# Sheet2.net
KiCad netlist of a schematic drawn in Altium Designer
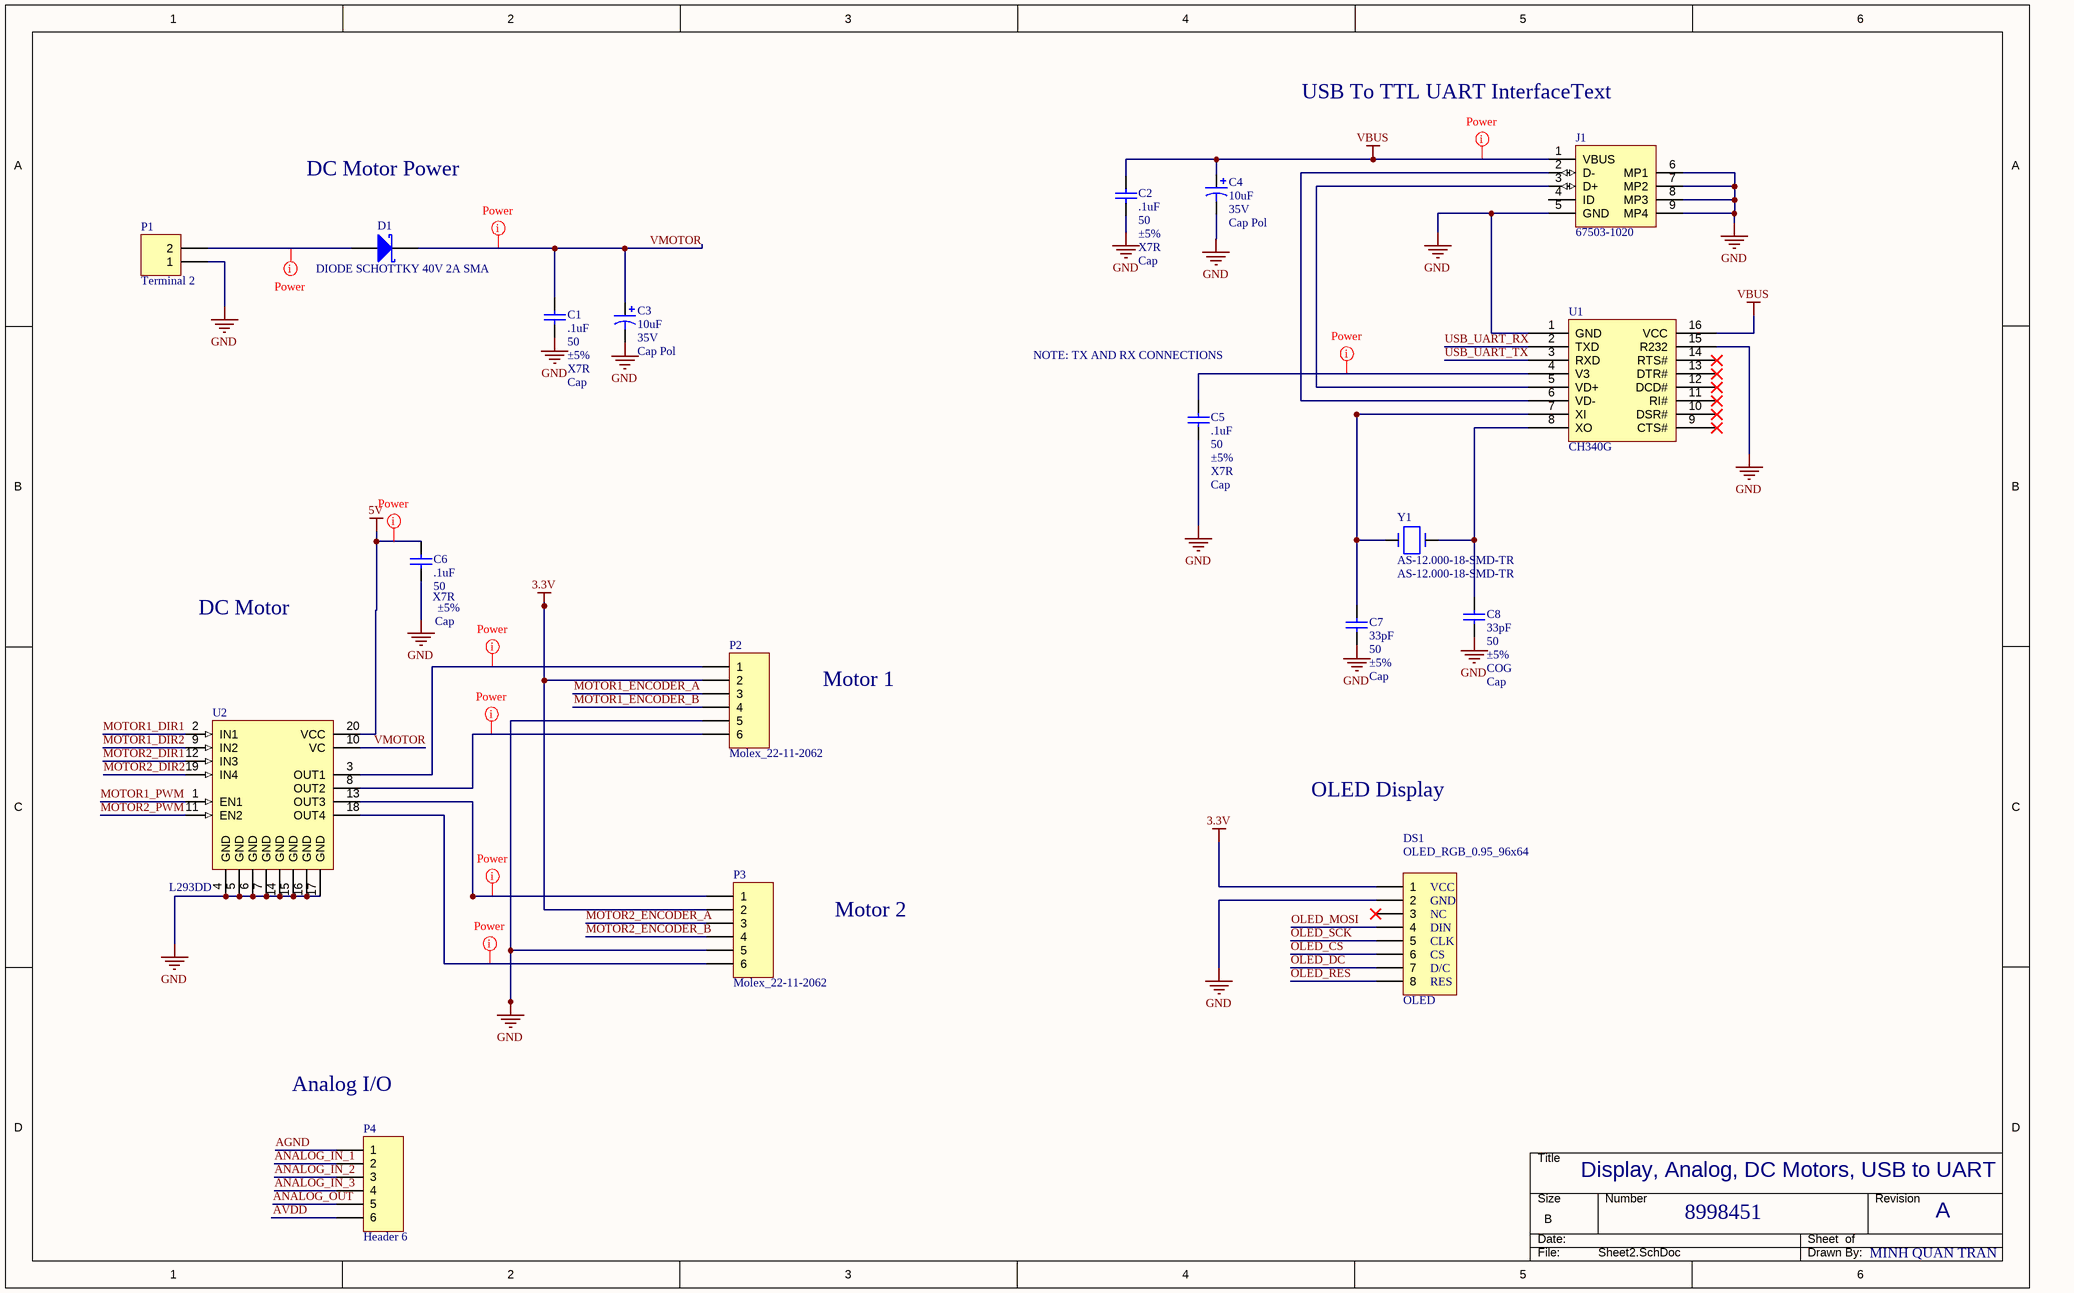
[diagram p0: Sheet2.SchDoc]

(export (version "E")
  (design (tool "Eeschema 10.0.6"))
  (components
    (comp (ref "C1")
      (value "Cap")
      (footprint "CAPC2012X09M")
      (description "CAP CER .1uF 50v X7R 0805")
      (fields
        (field (name "ALTIUM_VALUE") ".1uF")
        (field (name "WV") "50")
        (field (name "TOLERANCE") "±5%")
        (field (name "TYPE") "X7R")
        (field (name "MPN") "C0805C104J5RACTU")
      )
      (libsource (lib "esd_library") (part "CAP-X7R-.1uF-50V-±5%"))
    )
    (comp (ref "C2")
      (value "Cap")
      (footprint "CAPC2012X09M")
      (description "CAP CER .1uF 50v X7R 0805")
      (fields
        (field (name "ALTIUM_VALUE") ".1uF")
        (field (name "WV") "50")
        (field (name "TOLERANCE") "±5%")
        (field (name "TYPE") "X7R")
        (field (name "MPN") "C0805C104J5RACTU")
      )
      (libsource (lib "esd_library") (part "CAP-X7R-.1uF-50V-±5%"))
    )
    (comp (ref "C3")
      (value "Cap Pol")
      (footprint "CAPACITOR_5MM")
      (description "CAP 85C 10uF ±20% 35V WX Series Aluminum Electrolytic")
      (fields
        (field (name "ALTIUM_VALUE") "10uF")
        (field (name "VOLTAGE") "35V")
        (field (name "MPN") "UWX1V100MCL1GB")
      )
      (libsource (lib "esd_library") (part "Cap Polar-10uF-35V"))
    )
    (comp (ref "C4")
      (value "Cap Pol")
      (footprint "CAPACITOR_5MM")
      (description "CAP 85C 10uF ±20% 35V WX Series Aluminum Electrolytic")
      (fields
        (field (name "ALTIUM_VALUE") "10uF")
        (field (name "VOLTAGE") "35V")
        (field (name "MPN") "UWX1V100MCL1GB")
      )
      (libsource (lib "esd_library") (part "Cap Polar-10uF-35V"))
    )
    (comp (ref "C5")
      (value "Cap")
      (footprint "CAPC2012X09M")
      (description "CAP CER .1uF 50v X7R 0805")
      (fields
        (field (name "ALTIUM_VALUE") ".1uF")
        (field (name "WV") "50")
        (field (name "TOLERANCE") "±5%")
        (field (name "TYPE") "X7R")
        (field (name "MPN") "C0805C104J5RACTU")
      )
      (libsource (lib "esd_library") (part "CAP-X7R-.1uF-50V-±5%"))
    )
    (comp (ref "C6")
      (value "Cap")
      (footprint "CAPC2012X09M")
      (description "CAP CER .1uF 50v X7R 0805")
      (fields
        (field (name "ALTIUM_VALUE") ".1uF")
        (field (name "WV") "50")
        (field (name "TOLERANCE") "±5%")
        (field (name "TYPE") "X7R")
        (field (name "MPN") "C0805C104J5RACTU")
      )
      (libsource (lib "esd_library") (part "CAP-X7R-.1uF-50V-±5%"))
    )
    (comp (ref "C7")
      (value "Cap")
      (footprint "CAPC2012X09M")
      (description "CAP CER 33pF 50v COG 0805")
      (fields
        (field (name "ALTIUM_VALUE") "33pF")
        (field (name "WV") "50")
        (field (name "TOLERANCE") "±5%")
        (field (name "MPN") "C0805C330J5GACTU")
      )
      (libsource (lib "esd_library") (part "CAP-COG-33pF-50V-±5%"))
    )
    (comp (ref "C8")
      (value "Cap")
      (footprint "CAPC2012X09M")
      (description "CAP CER 33pF 50v COG 0805")
      (fields
        (field (name "ALTIUM_VALUE") "33pF")
        (field (name "WV") "50")
        (field (name "TOLERANCE") "±5%")
        (field (name "TYPE") "COG")
        (field (name "MPN") "C0805C330J5GACTU")
      )
      (libsource (lib "esd_library") (part "CAP-COG-33pF-50V-±5%"))
    )
    (comp (ref "D1")
      (value "DIODE SCHOTTKY 40V 2A SMA")
      (footprint "DIOM4326X23M")
      (description "Schottky Rectifier")
      (fields (field (name "MPN") "B240A-13-F"))
      (libsource (lib "esd_library") (part "DIODE SCHOTTKY 40V 2A SMA"))
    )
    (comp (ref "DS1")
      (value "OLED")
      (footprint "OLED_RGB_0.95_96x64_Waveshare")
      (description "Waveshare 0.95 inch OLED Module")
      (fields (field (name "MPN") "PPPC081LFBN-RC"))
      (libsource (lib "esd_library") (part "OLED_RGB_0.95_96x64_Waveshare"))
    )
    (comp (ref "J1")
      (value "67503-1020")
      (footprint "MOLX-67503-1020_V")
      (description "USB, MINI, SMD, RA KME04-USBMU03A01")
      (fields (field (name "MANUFACTURER") "Molex"))
      (libsource (lib "esd_library") (part "MOLX-67503-1020"))
    )
    (comp (ref "P1")
      (value "Terminal 2")
      (footprint "TYCO_282841_2")
      (description "Terminal, 2-Pin")
      (fields (field (name "MPN") "282841-2") (field (name "PUBLISHER") "Altium Limited"))
      (libsource (lib "esd_library") (part "Terminal 2"))
    )
    (comp (ref "P2")
      (value "Molex_22-11-2062")
      (footprint "MOLEX_22-11-2062")
      (description "CONN HEADER 6POS .100 VERT GOLD")
      (fields (field (name "MPN") "0022112062"))
      (libsource (lib "esd_library") (part "Molex_22-11-2062"))
    )
    (comp (ref "P3")
      (value "Molex_22-11-2062")
      (footprint "MOLEX_22-11-2062")
      (description "CONN HEADER 6POS .100 VERT GOLD")
      (fields (field (name "MPN") "0022112062"))
      (libsource (lib "esd_library") (part "Molex_22-11-2062"))
    )
    (comp (ref "P4")
      (value "Header 6")
      (footprint "HDR1X6")
      (description "Header, 6-Pin Male")
      (fields (field (name "MPN") "PEC06SFAN"))
      (libsource (lib "esd_library") (part "Header 6"))
    )
    (comp (ref "U1")
      (value "CH340G")
      (footprint "NSO16_L")
      (description "USB to serial chip")
      (libsource (lib "esd_library") (part "CH340G"))
    )
    (comp (ref "U2")
      (value "L293DD")
      (footprint "SO20_N")
      (description "IC MOTOR DRIVER PAR 20-SOIC")
      (fields (field (name "MPN") "L293DD013TR") (field (name "PUBLISHER") "Altium Limited"))
      (libsource (lib "esd_library") (part "L293DD"))
    )
    (comp (ref "Y1")
      (value "AS-12.000-18-SMD-TR")
      (footprint "HCS-49/U")
      (description "CRYSTAL 12.0000MHZ 18PF SMD")
      (fields (field (name "MPN") "AS-12.000-18-SMD-TR"))
      (libsource (lib "esd_library") (part "AS-12.000-18-SMD-TR"))
    )
  )
  (nets
    (net (code "1") (name "/AGND") (class "Default")
      (node (ref "P4") (pin "1") (pinfunction "1_1") (pintype "passive"))
    )
    (net (code "2") (name "/ANALOG_IN_1") (class "Default")
      (node (ref "P4") (pin "2") (pinfunction "2_2") (pintype "passive"))
    )
    (net (code "3") (name "/ANALOG_IN_2") (class "Default")
      (node (ref "P4") (pin "3") (pinfunction "3_3") (pintype "passive"))
    )
    (net (code "4") (name "/ANALOG_IN_3") (class "Default")
      (node (ref "P4") (pin "4") (pinfunction "4_4") (pintype "passive"))
    )
    (net (code "5") (name "/ANALOG_OUT") (class "Default")
      (node (ref "P4") (pin "5") (pinfunction "5_5") (pintype "passive"))
    )
    (net (code "6") (name "/AVDD") (class "Default")
      (node (ref "P4") (pin "6") (pinfunction "6_6") (pintype "passive"))
    )
    (net (code "7") (name "/MOTOR1_DIR1") (class "Default")
      (node (ref "U2") (pin "2") (pinfunction "IN1_2") (pintype "input"))
    )
    (net (code "8") (name "/MOTOR1_DIR2") (class "Default")
      (node (ref "U2") (pin "9") (pinfunction "IN2_9") (pintype "input"))
    )
    (net (code "9") (name "/MOTOR1_ENCODER_A") (class "Default")
      (node (ref "P2") (pin "3") (pinfunction "3_3") (pintype "passive"))
    )
    (net (code "10") (name "/MOTOR1_ENCODER_B") (class "Default")
      (node (ref "P2") (pin "4") (pinfunction "4_4") (pintype "passive"))
    )
    (net (code "11") (name "/MOTOR1_PWM") (class "Default")
      (node (ref "U2") (pin "1") (pinfunction "EN1_1") (pintype "input"))
    )
    (net (code "12") (name "/MOTOR2_DIR1") (class "Default")
      (node (ref "U2") (pin "12") (pinfunction "IN3_12") (pintype "input"))
    )
    (net (code "13") (name "/MOTOR2_DIR2") (class "Default")
      (node (ref "U2") (pin "19") (pinfunction "IN4_19") (pintype "input"))
    )
    (net (code "14") (name "/MOTOR2_ENCODER_A") (class "Default")
      (node (ref "P3") (pin "3") (pinfunction "3_3") (pintype "passive"))
    )
    (net (code "15") (name "/MOTOR2_ENCODER_B") (class "Default")
      (node (ref "P3") (pin "4") (pinfunction "4_4") (pintype "passive"))
    )
    (net (code "16") (name "/MOTOR2_PWM") (class "Default")
      (node (ref "U2") (pin "11") (pinfunction "EN2_11") (pintype "input"))
    )
    (net (code "17") (name "/OLED_CS") (class "Default")
      (node (ref "DS1") (pin "6") (pinfunction "6_6") (pintype "passive"))
    )
    (net (code "18") (name "/OLED_DC") (class "Default")
      (node (ref "DS1") (pin "7") (pinfunction "7_7") (pintype "passive"))
    )
    (net (code "19") (name "/OLED_MOSI") (class "Default")
      (node (ref "DS1") (pin "4") (pinfunction "4_4") (pintype "passive"))
    )
    (net (code "20") (name "/OLED_RES") (class "Default")
      (node (ref "DS1") (pin "8") (pinfunction "8_8") (pintype "passive"))
    )
    (net (code "21") (name "/OLED_SCK") (class "Default")
      (node (ref "DS1") (pin "5") (pinfunction "5_5") (pintype "passive"))
    )
    (net (code "22") (name "/USB_UART_RX") (class "Default")
      (node (ref "U1") (pin "2") (pinfunction "TXD_2") (pintype "passive"))
    )
    (net (code "23") (name "/USB_UART_TX") (class "Default")
      (node (ref "U1") (pin "3") (pinfunction "RXD_3") (pintype "passive"))
    )
    (net (code "24") (name "/VMOTOR") (class "Default")
      (node (ref "C1") (pin "2") (pinfunction "2_2") (pintype "passive"))
      (node (ref "C3") (pin "1") (pinfunction "1_1") (pintype "passive"))
      (node (ref "D1") (pin "1") (pinfunction "K_1") (pintype "passive"))
      (node (ref "U2") (pin "10") (pinfunction "VC_10") (pintype "power_in"))
    )
    (net (code "25") (name "3.3V") (class "Default")
      (node (ref "DS1") (pin "1") (pinfunction "1_1") (pintype "passive"))
      (node (ref "P2") (pin "2") (pinfunction "2_2") (pintype "passive"))
      (node (ref "P3") (pin "2") (pinfunction "2_2") (pintype "passive"))
    )
    (net (code "26") (name "5V") (class "Default")
      (node (ref "C6") (pin "2") (pinfunction "2_2") (pintype "passive"))
      (node (ref "U2") (pin "20") (pinfunction "VCC_20") (pintype "power_in"))
    )
    (net (code "27") (name "GND") (class "Default")
      (node (ref "C1") (pin "1") (pinfunction "1_1") (pintype "passive"))
      (node (ref "C2") (pin "2") (pinfunction "2_2") (pintype "passive"))
      (node (ref "C3") (pin "2") (pinfunction "2_2") (pintype "passive"))
      (node (ref "C4") (pin "2") (pinfunction "2_2") (pintype "passive"))
      (node (ref "C5") (pin "2") (pinfunction "2_2") (pintype "passive"))
      (node (ref "C6") (pin "1") (pinfunction "1_1") (pintype "passive"))
      (node (ref "C7") (pin "2") (pinfunction "2_2") (pintype "passive"))
      (node (ref "C8") (pin "2") (pinfunction "2_2") (pintype "passive"))
      (node (ref "DS1") (pin "2") (pinfunction "2_2") (pintype "passive"))
      (node (ref "J1") (pin "5") (pinfunction "GND_5") (pintype "power_in"))
      (node (ref "J1") (pin "6") (pinfunction "MP1_6") (pintype "passive"))
      (node (ref "J1") (pin "7") (pinfunction "MP2_7") (pintype "passive"))
      (node (ref "J1") (pin "8") (pinfunction "MP3_8") (pintype "passive"))
      (node (ref "J1") (pin "9") (pinfunction "MP4_9") (pintype "passive"))
      (node (ref "P1") (pin "1") (pinfunction "1_1") (pintype "passive"))
      (node (ref "P2") (pin "5") (pinfunction "5_5") (pintype "passive"))
      (node (ref "P3") (pin "5") (pinfunction "5_5") (pintype "passive"))
      (node (ref "U1") (pin "1") (pinfunction "GND_1") (pintype "passive"))
      (node (ref "U1") (pin "15") (pinfunction "R232_15") (pintype "passive"))
      (node (ref "U2") (pin "14") (pinfunction "GND_14") (pintype "power_in"))
      (node (ref "U2") (pin "15") (pinfunction "GND_15") (pintype "power_in"))
      (node (ref "U2") (pin "16") (pinfunction "GND_16") (pintype "power_in"))
      (node (ref "U2") (pin "17") (pinfunction "GND_17") (pintype "power_in"))
      (node (ref "U2") (pin "4") (pinfunction "GND_4") (pintype "power_in"))
      (node (ref "U2") (pin "5") (pinfunction "GND_5") (pintype "power_in"))
      (node (ref "U2") (pin "6") (pinfunction "GND_6") (pintype "power_in"))
      (node (ref "U2") (pin "7") (pinfunction "GND_7") (pintype "power_in"))
    )
    (net (code "28") (name "Net-(D1-A)") (class "Default")
      (node (ref "D1") (pin "2") (pinfunction "A_2") (pintype "passive"))
      (node (ref "P1") (pin "2") (pinfunction "2_2") (pintype "passive"))
    )
    (net (code "29") (name "Net-(J1-D+)") (class "Default")
      (node (ref "J1") (pin "3") (pinfunction "D+_3") (pintype "bidirectional"))
      (node (ref "U1") (pin "5") (pinfunction "VD+_5") (pintype "passive"))
    )
    (net (code "30") (name "Net-(J1-D-)") (class "Default")
      (node (ref "J1") (pin "2") (pinfunction "D-_2") (pintype "bidirectional"))
      (node (ref "U1") (pin "6") (pinfunction "VD-_6") (pintype "passive"))
    )
    (net (code "31") (name "Net-(U1-V3)") (class "Default")
      (node (ref "C5") (pin "1") (pinfunction "1_1") (pintype "passive"))
      (node (ref "U1") (pin "4") (pinfunction "V3_4") (pintype "passive"))
    )
    (net (code "32") (name "Net-(U1-XI)") (class "Default")
      (node (ref "C7") (pin "1") (pinfunction "1_1") (pintype "passive"))
      (node (ref "U1") (pin "7") (pinfunction "XI_7") (pintype "passive"))
      (node (ref "Y1") (pin "1") (pinfunction "1_1") (pintype "passive"))
    )
    (net (code "33") (name "Net-(U1-XO)") (class "Default")
      (node (ref "C8") (pin "1") (pinfunction "1_1") (pintype "passive"))
      (node (ref "U1") (pin "8") (pinfunction "XO_8") (pintype "passive"))
      (node (ref "Y1") (pin "2") (pinfunction "2_2") (pintype "passive"))
    )
    (net (code "34") (name "Net-(U2-OUT1)") (class "Default")
      (node (ref "P2") (pin "1") (pinfunction "1_1") (pintype "passive"))
      (node (ref "U2") (pin "3") (pinfunction "OUT1_3") (pintype "tri_state"))
    )
    (net (code "35") (name "Net-(U2-OUT2)") (class "Default")
      (node (ref "P2") (pin "6") (pinfunction "6_6") (pintype "passive"))
      (node (ref "U2") (pin "8") (pinfunction "OUT2_8") (pintype "tri_state"))
    )
    (net (code "36") (name "Net-(U2-OUT3)") (class "Default")
      (node (ref "P3") (pin "1") (pinfunction "1_1") (pintype "passive"))
      (node (ref "U2") (pin "13") (pinfunction "OUT3_13") (pintype "tri_state"))
    )
    (net (code "37") (name "Net-(U2-OUT4)") (class "Default")
      (node (ref "P3") (pin "6") (pinfunction "6_6") (pintype "passive"))
      (node (ref "U2") (pin "18") (pinfunction "OUT4_18") (pintype "tri_state"))
    )
    (net (code "38") (name "VBUS") (class "Default")
      (node (ref "C2") (pin "1") (pinfunction "1_1") (pintype "passive"))
      (node (ref "C4") (pin "1") (pinfunction "1_1") (pintype "passive"))
      (node (ref "J1") (pin "1") (pinfunction "VBUS_1") (pintype "power_in"))
      (node (ref "U1") (pin "16") (pinfunction "VCC_16") (pintype "passive"))
    )
    (net (code "39") (name "unconnected-(DS1-Pad3)") (class "Default")
      (node (ref "DS1") (pin "3") (pinfunction "3_3") (pintype "passive+no_connect"))
    )
    (net (code "40") (name "unconnected-(J1-ID-Pad4)") (class "Default")
      (node (ref "J1") (pin "4") (pinfunction "ID_4") (pintype "passive"))
    )
    (net (code "41") (name "unconnected-(U1-CTS#-Pad9)") (class "Default")
      (node (ref "U1") (pin "9") (pinfunction "CTS#_9") (pintype "passive+no_connect"))
    )
    (net (code "42") (name "unconnected-(U1-DCD#-Pad12)") (class "Default")
      (node (ref "U1") (pin "12") (pinfunction "DCD#_12") (pintype "passive+no_connect"))
    )
    (net (code "43") (name "unconnected-(U1-DSR#-Pad10)") (class "Default")
      (node (ref "U1") (pin "10") (pinfunction "DSR#_10") (pintype "passive+no_connect"))
    )
    (net (code "44") (name "unconnected-(U1-DTR#-Pad13)") (class "Default")
      (node (ref "U1") (pin "13") (pinfunction "DTR#_13") (pintype "passive+no_connect"))
    )
    (net (code "45") (name "unconnected-(U1-RI#-Pad11)") (class "Default")
      (node (ref "U1") (pin "11") (pinfunction "RI#_11") (pintype "passive+no_connect"))
    )
    (net (code "46") (name "unconnected-(U1-RTS#-Pad14)") (class "Default")
      (node (ref "U1") (pin "14") (pinfunction "RTS#_14") (pintype "passive+no_connect"))
    )
  )
)
